# 2020.net
KiCad netlist of a schematic drawn in Altium Designer
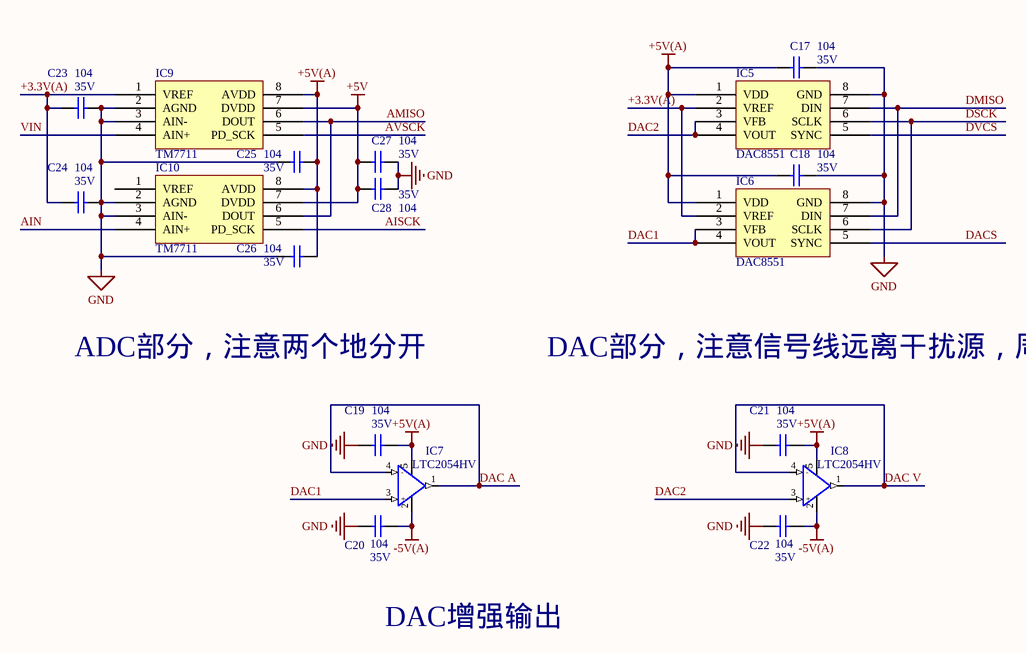
[diagram p0: 2020年电赛校赛测量、基准板.SchDoc]

(export (version "E")
  (design (tool "Eeschema 10.0.6"))
  (components
    (comp (ref "C17")
      (value "104")
      (footprint "C0805")
      (description "无极性电容")
      (fields (field (name "ALTIUM_VALUE") "35V"))
      (libsource (lib "原理图库") (part "104"))
    )
    (comp (ref "C18")
      (value "104")
      (footprint "C0805")
      (description "无极性电容")
      (fields (field (name "ALTIUM_VALUE") "35V"))
      (libsource (lib "原理图库") (part "104"))
    )
    (comp (ref "C19")
      (value "104")
      (footprint "C0805")
      (description "无极性电容")
      (fields (field (name "ALTIUM_VALUE") "35V"))
      (libsource (lib "原理图库") (part "104"))
    )
    (comp (ref "C20")
      (value "104")
      (footprint "C0805")
      (description "无极性电容")
      (fields (field (name "ALTIUM_VALUE") "35V"))
      (libsource (lib "原理图库") (part "104"))
    )
    (comp (ref "C21")
      (value "104")
      (footprint "C0805")
      (description "无极性电容")
      (fields (field (name "ALTIUM_VALUE") "35V"))
      (libsource (lib "原理图库") (part "104"))
    )
    (comp (ref "C22")
      (value "104")
      (footprint "C0805")
      (description "无极性电容")
      (fields (field (name "ALTIUM_VALUE") "35V"))
      (libsource (lib "原理图库") (part "104"))
    )
    (comp (ref "C23")
      (value "104")
      (footprint "C0805")
      (description "无极性电容")
      (fields (field (name "ALTIUM_VALUE") "35V"))
      (libsource (lib "原理图库") (part "104"))
    )
    (comp (ref "C24")
      (value "104")
      (footprint "C0805")
      (description "无极性电容")
      (fields (field (name "ALTIUM_VALUE") "35V"))
      (libsource (lib "原理图库") (part "104"))
    )
    (comp (ref "C25")
      (value "104")
      (footprint "C0805")
      (description "无极性电容")
      (fields (field (name "ALTIUM_VALUE") "35V"))
      (libsource (lib "原理图库") (part "104"))
    )
    (comp (ref "C26")
      (value "104")
      (footprint "C0805")
      (description "无极性电容")
      (fields (field (name "ALTIUM_VALUE") "35V"))
      (libsource (lib "原理图库") (part "104"))
    )
    (comp (ref "C27")
      (value "104")
      (footprint "C0805")
      (description "无极性电容")
      (fields (field (name "ALTIUM_VALUE") "35V"))
      (libsource (lib "原理图库") (part "104"))
    )
    (comp (ref "C28")
      (value "104")
      (footprint "C0805")
      (description "无极性电容")
      (fields (field (name "ALTIUM_VALUE") "35V"))
      (libsource (lib "原理图库") (part "104"))
    )
    (comp (ref "IC5") (value "DAC8551") (footprint "MSOP-8") (libsource (lib "Lib") (part "DAC8551")))
    (comp (ref "IC6") (value "DAC8551") (footprint "MSOP-8") (libsource (lib "Lib") (part "DAC8551")))
    (comp (ref "IC7")
      (value "LTC2054HV")
      (footprint "TSOT-32-5")
      (description "运放")
      (libsource (lib "原理图库") (part "OPA350UA"))
    )
    (comp (ref "IC8")
      (value "LTC2054HV")
      (footprint "TSOT-32-5")
      (description "运放")
      (libsource (lib "原理图库") (part "OPA350UA"))
    )
    (comp (ref "IC9") (value "TM7711") (footprint "SOP-8(体宽3.8mm)") (libsource (lib "Lib") (part "TM7711")))
    (comp (ref "IC10") (value "TM7711") (footprint "SOP-8(体宽3.8mm)") (libsource (lib "Lib") (part "TM7711")))
  )
  (nets
    (net (code "1") (name "+5V") (class "Default")
      (node (ref "C27") (pin "1") (pintype "passive"))
      (node (ref "C28") (pin "1") (pintype "passive"))
      (node (ref "IC10") (pin "7") (pinfunction "DVDD_7") (pintype "passive"))
      (node (ref "IC9") (pin "7") (pinfunction "DVDD_7") (pintype "passive"))
    )
    (net (code "2") (name "+5V(A)") (class "Default")
      (node (ref "C17") (pin "1") (pintype "passive"))
      (node (ref "C18") (pin "1") (pintype "passive"))
      (node (ref "C19") (pin "2") (pintype "passive"))
      (node (ref "C21") (pin "2") (pintype "passive"))
      (node (ref "C25") (pin "2") (pintype "passive"))
      (node (ref "C26") (pin "2") (pintype "passive"))
      (node (ref "IC10") (pin "8") (pinfunction "AVDD_8") (pintype "passive"))
      (node (ref "IC5") (pin "1") (pinfunction "VDD_1") (pintype "passive"))
      (node (ref "IC6") (pin "1") (pinfunction "VDD_1") (pintype "passive"))
      (node (ref "IC7") (pin "5") (pintype "passive"))
      (node (ref "IC8") (pin "5") (pintype "passive"))
      (node (ref "IC9") (pin "8") (pinfunction "AVDD_8") (pintype "passive"))
    )
    (net (code "3") (name "-5V(A)") (class "Default")
      (node (ref "C20") (pin "2") (pintype "passive"))
      (node (ref "C22") (pin "2") (pintype "passive"))
      (node (ref "IC7") (pin "2") (pintype "passive"))
      (node (ref "IC8") (pin "2") (pintype "passive"))
    )
    (net (code "4") (name "/+3.3V(A)") (class "Default")
      (node (ref "C23") (pin "1") (pintype "passive"))
      (node (ref "C24") (pin "1") (pintype "passive"))
      (node (ref "IC5") (pin "2") (pinfunction "VREF_2") (pintype "passive"))
      (node (ref "IC6") (pin "2") (pinfunction "VREF_2") (pintype "passive"))
      (node (ref "IC9") (pin "1") (pinfunction "VREF_1") (pintype "passive"))
    )
    (net (code "5") (name "/AIN") (class "Default")
      (node (ref "IC10") (pin "4") (pinfunction "AIN+_4") (pintype "passive"))
    )
    (net (code "6") (name "/AISCK") (class "Default")
      (node (ref "IC10") (pin "5") (pinfunction "PD_SCK_5") (pintype "passive"))
    )
    (net (code "7") (name "/AMISO") (class "Default")
      (node (ref "IC10") (pin "6") (pinfunction "DOUT_6") (pintype "passive"))
      (node (ref "IC9") (pin "6") (pinfunction "DOUT_6") (pintype "passive"))
    )
    (net (code "8") (name "/AVSCK") (class "Default")
      (node (ref "IC9") (pin "5") (pinfunction "PD_SCK_5") (pintype "passive"))
    )
    (net (code "9") (name "/DAC A") (class "Default")
      (node (ref "IC7") (pin "1") (pintype "output"))
      (node (ref "IC7") (pin "4") (pinfunction "-_4") (pintype "input"))
    )
    (net (code "10") (name "/DAC V") (class "Default")
      (node (ref "IC8") (pin "1") (pintype "output"))
      (node (ref "IC8") (pin "4") (pinfunction "-_4") (pintype "input"))
    )
    (net (code "11") (name "/DAC1") (class "Default")
      (node (ref "IC6") (pin "3") (pinfunction "VFB_3") (pintype "passive"))
      (node (ref "IC6") (pin "4") (pinfunction "VOUT_4") (pintype "passive"))
      (node (ref "IC7") (pin "3") (pinfunction "+_3") (pintype "input"))
    )
    (net (code "12") (name "/DAC2") (class "Default")
      (node (ref "IC5") (pin "3") (pinfunction "VFB_3") (pintype "passive"))
      (node (ref "IC5") (pin "4") (pinfunction "VOUT_4") (pintype "passive"))
      (node (ref "IC8") (pin "3") (pinfunction "+_3") (pintype "input"))
    )
    (net (code "13") (name "/DACS") (class "Default")
      (node (ref "IC6") (pin "5") (pinfunction "SYNC_5") (pintype "passive"))
    )
    (net (code "14") (name "/DMISO") (class "Default")
      (node (ref "IC5") (pin "7") (pinfunction "DIN_7") (pintype "passive"))
      (node (ref "IC6") (pin "7") (pinfunction "DIN_7") (pintype "passive"))
    )
    (net (code "15") (name "/DSCK") (class "Default")
      (node (ref "IC5") (pin "6") (pinfunction "SCLK_6") (pintype "passive"))
      (node (ref "IC6") (pin "6") (pinfunction "SCLK_6") (pintype "passive"))
    )
    (net (code "16") (name "/DVCS") (class "Default")
      (node (ref "IC5") (pin "5") (pinfunction "SYNC_5") (pintype "passive"))
    )
    (net (code "17") (name "/VIN") (class "Default")
      (node (ref "IC9") (pin "4") (pinfunction "AIN+_4") (pintype "passive"))
    )
    (net (code "18") (name "GND") (class "Default")
      (node (ref "C17") (pin "2") (pintype "passive"))
      (node (ref "C18") (pin "2") (pintype "passive"))
      (node (ref "C19") (pin "1") (pintype "passive"))
      (node (ref "C20") (pin "1") (pintype "passive"))
      (node (ref "C21") (pin "1") (pintype "passive"))
      (node (ref "C22") (pin "1") (pintype "passive"))
      (node (ref "C23") (pin "2") (pintype "passive"))
      (node (ref "C24") (pin "2") (pintype "passive"))
      (node (ref "C25") (pin "1") (pintype "passive"))
      (node (ref "C26") (pin "1") (pintype "passive"))
      (node (ref "C27") (pin "2") (pintype "passive"))
      (node (ref "C28") (pin "2") (pintype "passive"))
      (node (ref "IC10") (pin "2") (pinfunction "AGND_2") (pintype "passive"))
      (node (ref "IC10") (pin "3") (pinfunction "AIN-_3") (pintype "passive"))
      (node (ref "IC5") (pin "8") (pinfunction "GND_8") (pintype "passive"))
      (node (ref "IC6") (pin "8") (pinfunction "GND_8") (pintype "passive"))
      (node (ref "IC9") (pin "2") (pinfunction "AGND_2") (pintype "passive"))
      (node (ref "IC9") (pin "3") (pinfunction "AIN-_3") (pintype "passive"))
    )
    (net (code "19") (name "unconnected-(IC10-VREF-Pad1)") (class "Default")
      (node (ref "IC10") (pin "1") (pinfunction "VREF_1") (pintype "passive"))
    )
  )
)
